# McPiFace-60mmFan-V2.net
KiCad netlist of a schematic drawn in EAGLE
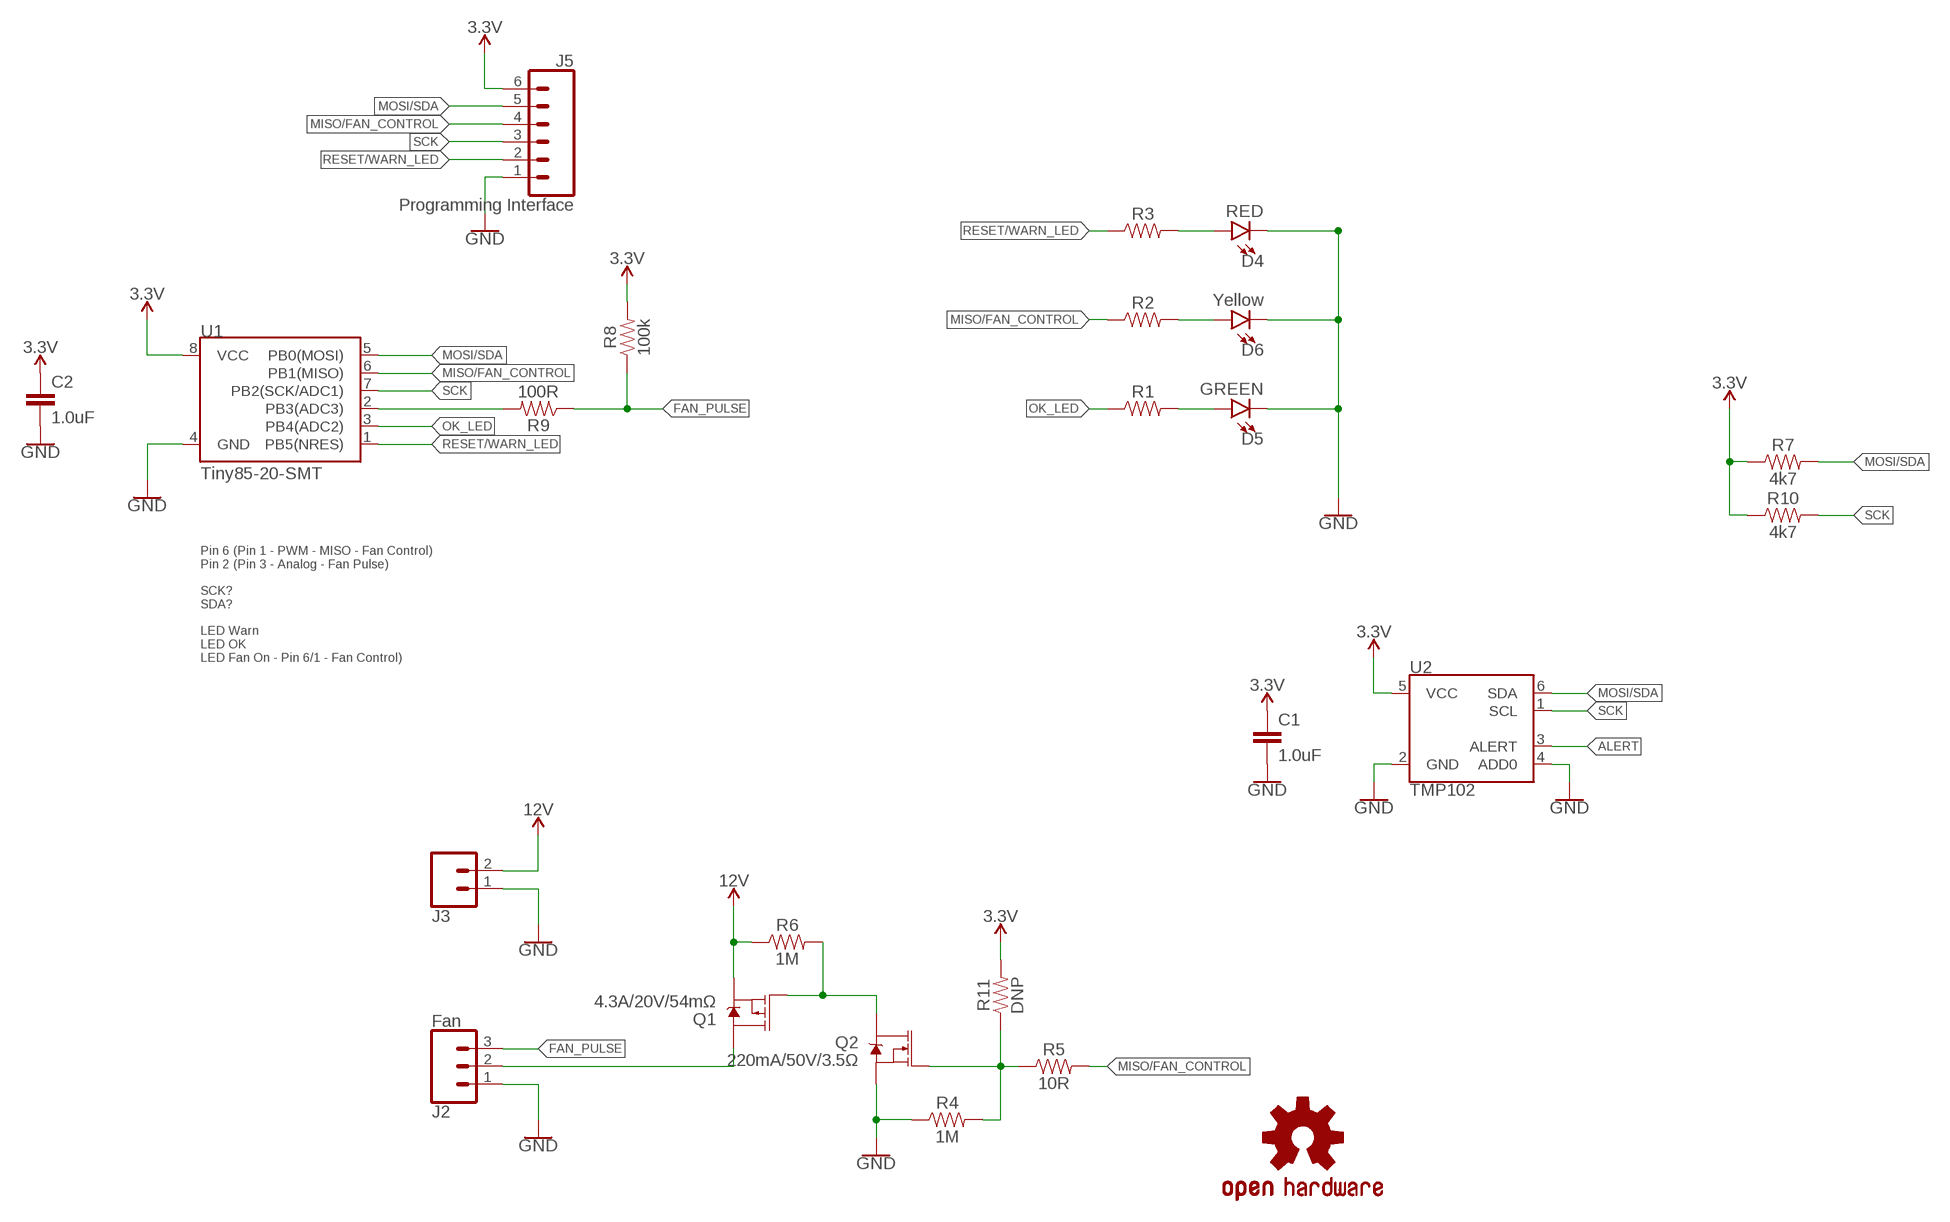
[diagram p0: schematic, sheet 1]

(export (version "E")
  (design (tool "Eeschema 10.0.6"))
  (components
    (comp (ref "C1")
      (value "1.0uF")
      (footprint "eagle-import:0805")
      (libsource (lib "eagle-import") (part "1.0UF-0805-25V-10%"))
    )
    (comp (ref "C2")
      (value "1.0uF")
      (footprint "eagle-import:0805")
      (libsource (lib "eagle-import") (part "1.0UF-0805-25V-10%"))
    )
    (comp (ref "D4")
      (value "RED")
      (footprint "eagle-import:LED-1206")
      (libsource (lib "eagle-import") (part "LED-RED1206"))
    )
    (comp (ref "D5")
      (value "GREEN")
      (footprint "eagle-import:LED-1206")
      (libsource (lib "eagle-import") (part "LED-GREEN1206"))
    )
    (comp (ref "D6")
      (value "Yellow")
      (footprint "eagle-import:LED-1206")
      (libsource (lib "eagle-import") (part "LED-YELLOWLILYPAD"))
    )
    (comp (ref "J2")
      (value "Fan")
      (footprint "eagle-import:JST-3-SMD")
      (fields (field (name "MFG") "S3B-PH-SM4-TB(LF)(SN)"))
      (libsource (lib "eagle-import") (part "CONN_03JST-SMD"))
    )
    (comp (ref "J3")
      (value "CONN_02-JST-2MM-SMT")
      (footprint "eagle-import:JST-2-SMD")
      (fields (field (name "MFG") "S2B-PH-SM4-TB(LF)(SN)"))
      (libsource (lib "eagle-import") (part "CONN_02-JST-2MM-SMT"))
    )
    (comp (ref "J5")
      (value "Programming Interface")
      (footprint "eagle-import:1X06-1MM")
      (libsource (lib "eagle-import") (part "CONN_06SMD-1MM"))
    )
    (comp (ref "LOGO1")
      (value "OSHW-LOGOL")
      (footprint "eagle-import:OSHW-LOGO-L")
      (libsource (lib "eagle-import") (part "OSHW-LOGOL"))
    )
    (comp (ref "Q1")
      (value "4.3A/20V/54mΩ")
      (footprint "eagle-import:SOT23-3")
      (libsource (lib "eagle-import") (part "MOSFET_PCH-IRLML2244"))
    )
    (comp (ref "Q2")
      (value "220mA/50V/3.5Ω")
      (footprint "eagle-import:SOT23-3")
      (libsource (lib "eagle-import") (part "MOSFET-NCH-BSS138"))
    )
    (comp (ref "R1")
      (value "RESISTOR1206")
      (footprint "eagle-import:1206")
      (libsource (lib "eagle-import") (part "RESISTOR1206"))
    )
    (comp (ref "R2")
      (value "RESISTOR1206")
      (footprint "eagle-import:1206")
      (libsource (lib "eagle-import") (part "RESISTOR1206"))
    )
    (comp (ref "R3")
      (value "RESISTOR1206")
      (footprint "eagle-import:1206")
      (libsource (lib "eagle-import") (part "RESISTOR1206"))
    )
    (comp (ref "R4")
      (value "1M")
      (footprint "eagle-import:0805")
      (libsource (lib "eagle-import") (part "RESISTOR0805"))
    )
    (comp (ref "R5")
      (value "10R")
      (footprint "eagle-import:0805")
      (libsource (lib "eagle-import") (part "RESISTOR0805"))
    )
    (comp (ref "R6")
      (value "1M")
      (footprint "eagle-import:0805")
      (libsource (lib "eagle-import") (part "RESISTOR0805"))
    )
    (comp (ref "R7")
      (value "4k7")
      (footprint "eagle-import:0805")
      (libsource (lib "eagle-import") (part "RESISTOR0805"))
    )
    (comp (ref "R8")
      (value "100k")
      (footprint "eagle-import:0805")
      (libsource (lib "eagle-import") (part "RESISTOR0805"))
    )
    (comp (ref "R9")
      (value "100R")
      (footprint "eagle-import:0805")
      (libsource (lib "eagle-import") (part "RESISTOR0805"))
    )
    (comp (ref "R10")
      (value "4k7")
      (footprint "eagle-import:0805")
      (libsource (lib "eagle-import") (part "RESISTOR0805"))
    )
    (comp (ref "R11")
      (value "DNP")
      (footprint "eagle-import:0805")
      (libsource (lib "eagle-import") (part "RESISTOR0805"))
    )
    (comp (ref "U1")
      (value "Tiny85-20-SMT")
      (footprint "eagle-import:SO08-EIAJ")
      (libsource (lib "eagle-import") (part "ATTINY45TINY85-20-SMT"))
    )
    (comp (ref "U2")
      (value "TMP102")
      (footprint "eagle-import:SOT563")
      (libsource (lib "eagle-import") (part "TMP102"))
    )
  )
  (nets
    (net (code "1") (name "3.3V") (class "Default")
      (node (ref "C1") (pin "1") (pinfunction "1_1") (pintype "passive"))
      (node (ref "C2") (pin "1") (pinfunction "1_1") (pintype "passive"))
      (node (ref "J5") (pin "6") (pinfunction "6_6") (pintype "passive"))
      (node (ref "R10") (pin "1") (pinfunction "1_1") (pintype "passive"))
      (node (ref "R11") (pin "2") (pinfunction "2_2") (pintype "passive"))
      (node (ref "R7") (pin "1") (pinfunction "1_1") (pintype "passive"))
      (node (ref "R8") (pin "2") (pinfunction "2_2") (pintype "passive"))
      (node (ref "U1") (pin "8") (pinfunction "VCC_8") (pintype "bidirectional"))
      (node (ref "U2") (pin "5") (pinfunction "VCC_5") (pintype "bidirectional"))
    )
    (net (code "2") (name "12V") (class "Default")
      (node (ref "J3") (pin "2") (pinfunction "1_2") (pintype "passive"))
      (node (ref "Q1") (pin "2") (pinfunction "S_2") (pintype "bidirectional"))
      (node (ref "R6") (pin "1") (pinfunction "1_1") (pintype "passive"))
    )
    (net (code "3") (name "ALERT") (class "Default")
      (node (ref "U2") (pin "3") (pinfunction "ALERT_3") (pintype "bidirectional"))
    )
    (net (code "4") (name "FAN_PULSE") (class "Default")
      (node (ref "J2") (pin "3") (pinfunction "1_3") (pintype "passive"))
      (node (ref "R8") (pin "1") (pinfunction "1_1") (pintype "passive"))
      (node (ref "R9") (pin "1") (pinfunction "1_1") (pintype "passive"))
    )
    (net (code "5") (name "GND") (class "Default")
      (node (ref "C1") (pin "2") (pinfunction "2_2") (pintype "passive"))
      (node (ref "C2") (pin "2") (pinfunction "2_2") (pintype "passive"))
      (node (ref "D4") (pin "C") (pinfunction "C_C") (pintype "passive"))
      (node (ref "D5") (pin "C") (pinfunction "C_C") (pintype "passive"))
      (node (ref "D6") (pin "C") (pinfunction "C_C") (pintype "passive"))
      (node (ref "J2") (pin "1") (pinfunction "3_1") (pintype "passive"))
      (node (ref "J3") (pin "1") (pinfunction "2_1") (pintype "passive"))
      (node (ref "J5") (pin "1") (pinfunction "1_1") (pintype "passive"))
      (node (ref "Q2") (pin "2") (pinfunction "S_2") (pintype "bidirectional"))
      (node (ref "R4") (pin "1") (pinfunction "1_1") (pintype "passive"))
      (node (ref "U1") (pin "4") (pinfunction "GND_4") (pintype "bidirectional"))
      (node (ref "U2") (pin "2") (pinfunction "GND_2") (pintype "bidirectional"))
      (node (ref "U2") (pin "4") (pinfunction "ADD0_4") (pintype "bidirectional"))
    )
    (net (code "6") (name "MISO{slash}FAN_CONTROL") (class "Default")
      (node (ref "J5") (pin "4") (pinfunction "4_4") (pintype "passive"))
      (node (ref "R2") (pin "1") (pinfunction "1_1") (pintype "passive"))
      (node (ref "R5") (pin "2") (pinfunction "2_2") (pintype "passive"))
      (node (ref "U1") (pin "6") (pinfunction "PB1(MISO)_6") (pintype "bidirectional"))
    )
    (net (code "7") (name "MOSI{slash}SDA") (class "Default")
      (node (ref "J5") (pin "5") (pinfunction "5_5") (pintype "passive"))
      (node (ref "R7") (pin "2") (pinfunction "2_2") (pintype "passive"))
      (node (ref "U1") (pin "5") (pinfunction "PB0(MOSI)_5") (pintype "bidirectional"))
      (node (ref "U2") (pin "6") (pinfunction "SDA_6") (pintype "bidirectional"))
    )
    (net (code "8") (name "Net-(D4-PadA)") (class "Default")
      (node (ref "D4") (pin "A") (pinfunction "A_A") (pintype "passive"))
      (node (ref "R3") (pin "2") (pinfunction "2_2") (pintype "passive"))
    )
    (net (code "9") (name "Net-(D5-PadA)") (class "Default")
      (node (ref "D5") (pin "A") (pinfunction "A_A") (pintype "passive"))
      (node (ref "R1") (pin "2") (pinfunction "2_2") (pintype "passive"))
    )
    (net (code "10") (name "Net-(D6-PadA)") (class "Default")
      (node (ref "D6") (pin "A") (pinfunction "A_A") (pintype "passive"))
      (node (ref "R2") (pin "2") (pinfunction "2_2") (pintype "passive"))
    )
    (net (code "11") (name "Net-(Q1-D)") (class "Default")
      (node (ref "J2") (pin "2") (pinfunction "2_2") (pintype "passive"))
      (node (ref "Q1") (pin "3") (pinfunction "D_3") (pintype "bidirectional"))
    )
    (net (code "12") (name "Net-(Q1-G)") (class "Default")
      (node (ref "Q1") (pin "1") (pinfunction "G_1") (pintype "bidirectional"))
      (node (ref "Q2") (pin "3") (pinfunction "D_3") (pintype "bidirectional"))
      (node (ref "R6") (pin "2") (pinfunction "2_2") (pintype "passive"))
    )
    (net (code "13") (name "Net-(Q2-G)") (class "Default")
      (node (ref "Q2") (pin "1") (pinfunction "G_1") (pintype "bidirectional"))
      (node (ref "R11") (pin "1") (pinfunction "1_1") (pintype "passive"))
      (node (ref "R4") (pin "2") (pinfunction "2_2") (pintype "passive"))
      (node (ref "R5") (pin "1") (pinfunction "1_1") (pintype "passive"))
    )
    (net (code "14") (name "Net-(U1-PB3(ADC3))") (class "Default")
      (node (ref "R9") (pin "2") (pinfunction "2_2") (pintype "passive"))
      (node (ref "U1") (pin "2") (pinfunction "PB3(ADC3)_2") (pintype "bidirectional"))
    )
    (net (code "15") (name "OK_LED") (class "Default")
      (node (ref "R1") (pin "1") (pinfunction "1_1") (pintype "passive"))
      (node (ref "U1") (pin "3") (pinfunction "PB4(ADC2)_3") (pintype "bidirectional"))
    )
    (net (code "16") (name "RESET{slash}WARN_LED") (class "Default")
      (node (ref "J5") (pin "2") (pinfunction "2_2") (pintype "passive"))
      (node (ref "R3") (pin "1") (pinfunction "1_1") (pintype "passive"))
      (node (ref "U1") (pin "1") (pinfunction "PB5(NRES)_1") (pintype "bidirectional"))
    )
    (net (code "17") (name "SCK") (class "Default")
      (node (ref "J5") (pin "3") (pinfunction "3_3") (pintype "passive"))
      (node (ref "R10") (pin "2") (pinfunction "2_2") (pintype "passive"))
      (node (ref "U1") (pin "7") (pinfunction "PB2(SCK/ADC1)_7") (pintype "bidirectional"))
      (node (ref "U2") (pin "1") (pinfunction "SCL_1") (pintype "bidirectional"))
    )
  )
)
